# 6_GPS.net
KiCad netlist of a schematic drawn in Altium Designer
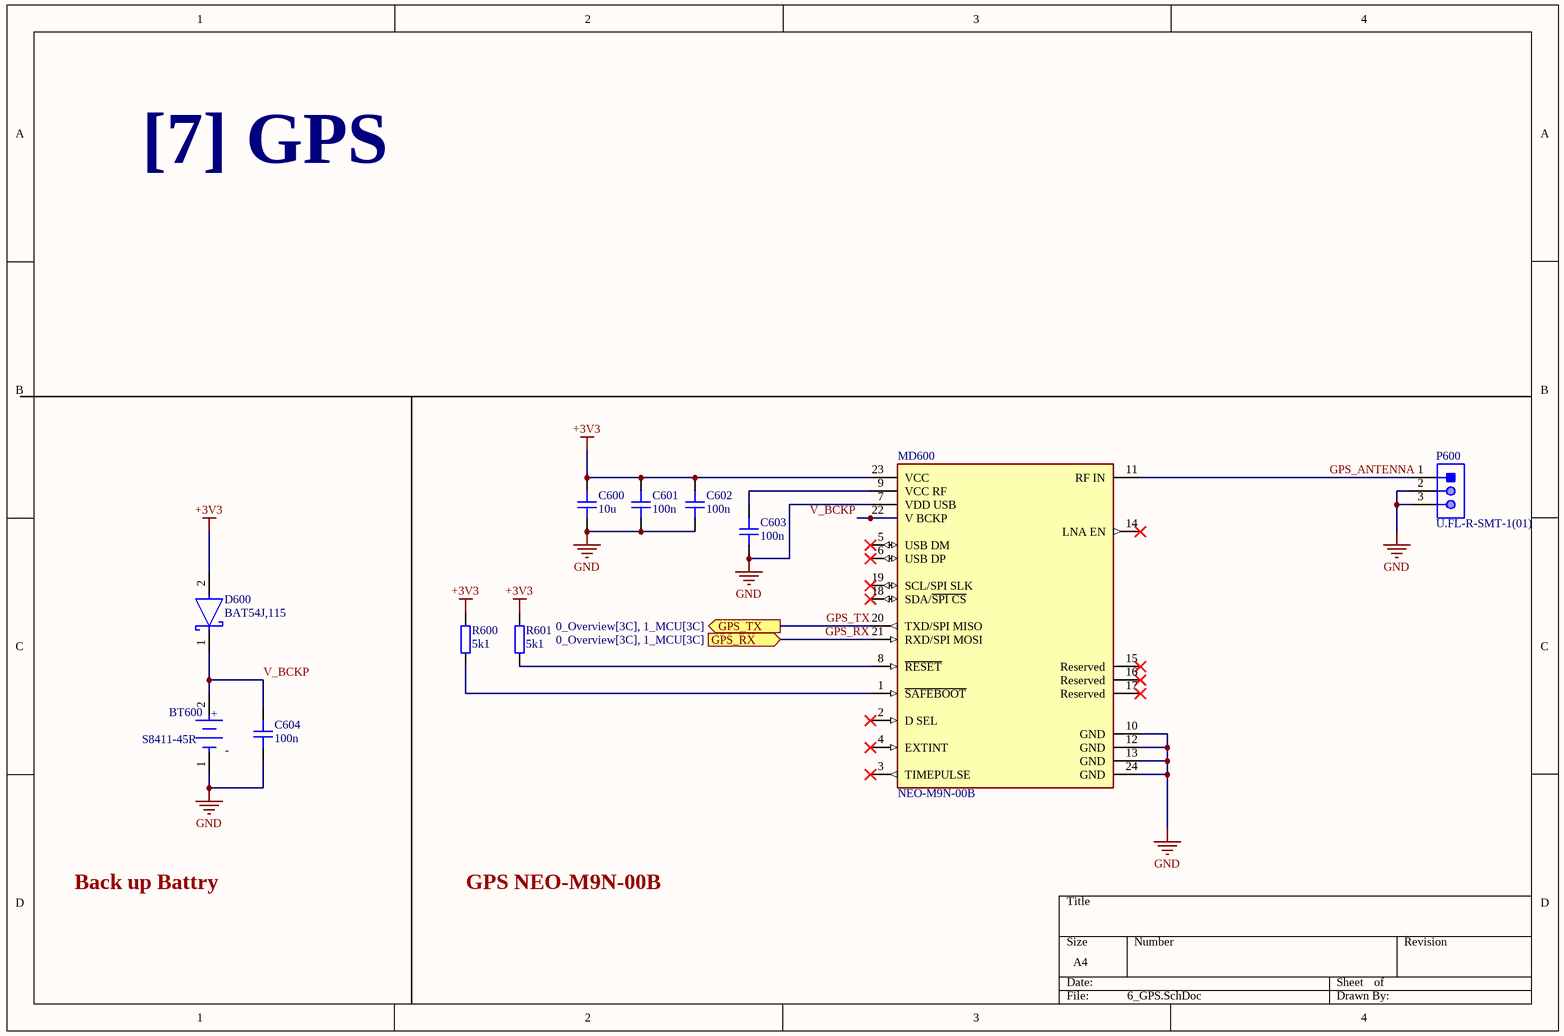
[diagram p0: 6_GPS.SchDoc]

(export (version "E")
  (design (tool "Eeschema 10.0.6"))
  (components
    (comp (ref "BT600")
      (value "S8411-45R")
      (footprint "FP-S8411-45R-MFG")
      (description "BATTERY HOLDER COIN 12MM SMD")
      (libsource (lib "Altium Content Vault") (part "60d3b5b901a8747834971d0eb8cf3fd"))
    )
    (comp (ref "C600")
      (value "10u")
      (footprint "CAP_0805")
      (description "Capacitor SMD 0805")
      (libsource (lib "Schematic-Lib-PhilsLab") (part "CAP_0805"))
    )
    (comp (ref "C601")
      (value "100n")
      (footprint "CAP_0603")
      (description "Capacitor SMD 0603")
      (libsource (lib "Schematic-Lib-PhilsLab") (part "CAP_0603"))
    )
    (comp (ref "C602")
      (value "100n")
      (footprint "CAP_0603")
      (description "Capacitor SMD 0603")
      (libsource (lib "Schematic-Lib-PhilsLab") (part "CAP_0603"))
    )
    (comp (ref "C603")
      (value "100n")
      (footprint "CAP_0603")
      (description "Capacitor SMD 0603")
      (libsource (lib "Schematic-Lib-PhilsLab") (part "CAP_0603"))
    )
    (comp (ref "C604")
      (value "100n")
      (footprint "CAP_0603")
      (description "Capacitor SMD 0603")
      (libsource (lib "Schematic-Lib-PhilsLab") (part "CAP_0603"))
    )
    (comp (ref "D600")
      (value "BAT54J,115")
      (footprint "FP-SOD323F-MFG")
      (description "DIODE SCHOTTKY 30V 200MA SOD323F")
      (libsource (lib "Altium Content Vault") (part "1d6ec82d83fb6aee721767c19dac4b9"))
    )
    (comp (ref "MD600")
      (value "NEO-M9N-00B")
      (footprint "FP-NEO-M9N-00B-MFG")
      (description "M9 standard precision module")
      (fields
        (field (name "MANUFACTURER") "u-blox")
        (field (name "OCTOPART") "https://octopart.com/neo-m9n-00b-u-blox-107315722")
      )
      (libsource (lib "Altium Content Vault") (part "6afc83350215ab330c065e89349577f"))
    )
    (comp (ref "P600")
      (value "U.FL-R-SMT-1(01)")
      (footprint "HRS-U.FL-R-SMT-3_V")
      (description "Ultra Small Coaxial Connector, 6 GHz, -40 to 90 degC, 3-Pin SMD, RoHS, Bulk")
      (fields (field (name "MANUFACTURER") "Hirose Electric"))
      (libsource (lib "Altium Content Vault") (part "CN-1P-M-R3"))
    )
    (comp (ref "R600")
      (value "5k1")
      (footprint "RES_0603")
      (description "Resistor SMD 0603")
      (libsource (lib "Schematic-Lib-PhilsLab") (part "RES_0603"))
    )
    (comp (ref "R601")
      (value "5k1")
      (footprint "RES_0603")
      (description "Resistor SMD 0603")
      (libsource (lib "Schematic-Lib-PhilsLab") (part "RES_0603"))
    )
  )
  (nets
    (net (code "1") (name "+3V3") (class "Default")
      (node (ref "C600") (pin "2") (pinfunction "2_2") (pintype "passive"))
      (node (ref "C601") (pin "1") (pinfunction "1_1") (pintype "passive"))
      (node (ref "C602") (pin "1") (pinfunction "1_1") (pintype "passive"))
      (node (ref "D600") (pin "2") (pinfunction "A_2") (pintype "passive"))
      (node (ref "MD600") (pin "23") (pinfunction "VCC_23") (pintype "power_in"))
      (node (ref "R600") (pin "2") (pinfunction "2_2") (pintype "passive"))
      (node (ref "R601") (pin "2") (pinfunction "2_2") (pintype "passive"))
    )
    (net (code "2") (name "/GPS_ANTENNA") (class "Default")
      (node (ref "MD600") (pin "11") (pinfunction "RF_IN_11") (pintype "passive"))
      (node (ref "P600") (pin "1") (pinfunction "1_1") (pintype "passive"))
    )
    (net (code "3") (name "/GPS_RX") (class "Default")
      (node (ref "MD600") (pin "21") (pinfunction "RXD/SPI_MOSI_21") (pintype "input"))
    )
    (net (code "4") (name "/GPS_TX") (class "Default")
      (node (ref "MD600") (pin "20") (pinfunction "TXD/SPI_MISO_20") (pintype "output"))
    )
    (net (code "5") (name "/V_BCKP") (class "Default")
      (node (ref "BT600") (pin "2") (pinfunction "A_2") (pintype "passive"))
      (node (ref "C604") (pin "1") (pinfunction "1_1") (pintype "passive"))
      (node (ref "D600") (pin "1") (pinfunction "C_1") (pintype "passive"))
      (node (ref "MD600") (pin "22") (pinfunction "V_BCKP_22") (pintype "power_in"))
    )
    (net (code "6") (name "GND") (class "Default")
      (node (ref "BT600") (pin "1") (pinfunction "C_1") (pintype "passive"))
      (node (ref "C600") (pin "1") (pinfunction "1_1") (pintype "passive"))
      (node (ref "C601") (pin "2") (pinfunction "2_2") (pintype "passive"))
      (node (ref "C602") (pin "2") (pinfunction "2_2") (pintype "passive"))
      (node (ref "C603") (pin "2") (pinfunction "2_2") (pintype "passive"))
      (node (ref "C604") (pin "2") (pinfunction "2_2") (pintype "passive"))
      (node (ref "MD600") (pin "10") (pinfunction "GND_10") (pintype "power_in"))
      (node (ref "MD600") (pin "12") (pinfunction "GND_12") (pintype "power_in"))
      (node (ref "MD600") (pin "13") (pinfunction "GND_13") (pintype "power_in"))
      (node (ref "MD600") (pin "24") (pinfunction "GND_24") (pintype "power_in"))
      (node (ref "MD600") (pin "7") (pinfunction "VDD_USB_7") (pintype "power_in"))
      (node (ref "P600") (pin "2") (pinfunction "2_2") (pintype "passive"))
      (node (ref "P600") (pin "3") (pinfunction "3_3") (pintype "passive"))
    )
    (net (code "7") (name "Net-(MD600-VCC_RF)") (class "Default")
      (node (ref "C603") (pin "1") (pinfunction "1_1") (pintype "passive"))
      (node (ref "MD600") (pin "9") (pinfunction "VCC_RF_9") (pintype "power_in"))
    )
    (net (code "8") (name "Net-(MD600-~{RESET})") (class "Default")
      (node (ref "MD600") (pin "8") (pinfunction "~{RESET}_8") (pintype "input"))
      (node (ref "R601") (pin "1") (pinfunction "1_1") (pintype "passive"))
    )
    (net (code "9") (name "Net-(MD600-~{SAFEBOOT})") (class "Default")
      (node (ref "MD600") (pin "1") (pinfunction "~{SAFEBOOT}_1") (pintype "input"))
      (node (ref "R600") (pin "1") (pinfunction "1_1") (pintype "passive"))
    )
    (net (code "10") (name "unconnected-(MD600-D_SEL-Pad2)") (class "Default")
      (node (ref "MD600") (pin "2") (pinfunction "D_SEL_2") (pintype "input+no_connect"))
    )
    (net (code "11") (name "unconnected-(MD600-EXTINT-Pad4)") (class "Default")
      (node (ref "MD600") (pin "4") (pinfunction "EXTINT_4") (pintype "input+no_connect"))
    )
    (net (code "12") (name "unconnected-(MD600-LNA_EN-Pad14)") (class "Default")
      (node (ref "MD600") (pin "14") (pinfunction "LNA_EN_14") (pintype "output+no_connect"))
    )
    (net (code "13") (name "unconnected-(MD600-Reserved-Pad15)") (class "Default")
      (node (ref "MD600") (pin "15") (pinfunction "Reserved_15") (pintype "passive+no_connect"))
    )
    (net (code "14") (name "unconnected-(MD600-Reserved-Pad16)") (class "Default")
      (node (ref "MD600") (pin "16") (pinfunction "Reserved_16") (pintype "passive+no_connect"))
    )
    (net (code "15") (name "unconnected-(MD600-Reserved-Pad17)") (class "Default")
      (node (ref "MD600") (pin "17") (pinfunction "Reserved_17") (pintype "passive+no_connect"))
    )
    (net (code "16") (name "unconnected-(MD600-SCL{slash}SPI_SLK-Pad19)") (class "Default")
      (node (ref "MD600") (pin "19") (pinfunction "SCL/SPI_SLK_19") (pintype "bidirectional+no_connect"))
    )
    (net (code "17") (name "unconnected-(MD600-SDA{slash}~{SPI_CS}-Pad18)") (class "Default")
      (node (ref "MD600") (pin "18") (pinfunction "SDA/~{SPI_CS}_18") (pintype "bidirectional+no_connect"))
    )
    (net (code "18") (name "unconnected-(MD600-TIMEPULSE-Pad3)") (class "Default")
      (node (ref "MD600") (pin "3") (pinfunction "TIMEPULSE_3") (pintype "output+no_connect"))
    )
    (net (code "19") (name "unconnected-(MD600-USB_DM-Pad5)") (class "Default")
      (node (ref "MD600") (pin "5") (pinfunction "USB_DM_5") (pintype "bidirectional+no_connect"))
    )
    (net (code "20") (name "unconnected-(MD600-USB_DP-Pad6)") (class "Default")
      (node (ref "MD600") (pin "6") (pinfunction "USB_DP_6") (pintype "bidirectional+no_connect"))
    )
  )
)
